# Raspi_Photometer_v2.net
KiCad netlist of a schematic drawn in EAGLE
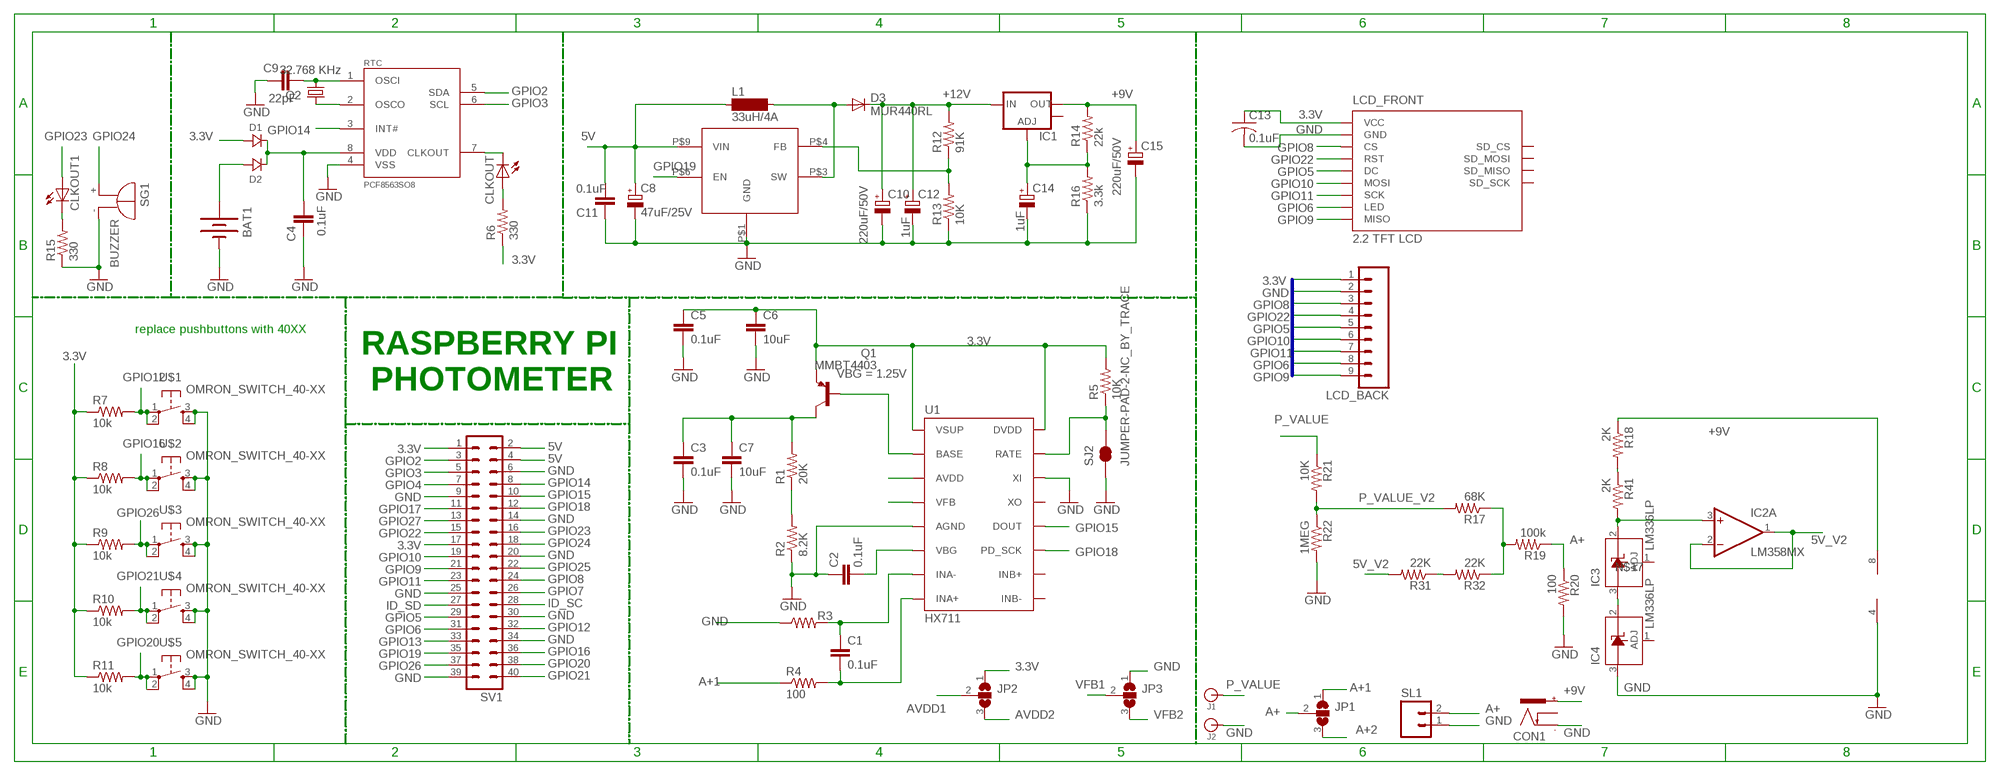
[diagram p0: schematic, sheet 1]

(export (version "E")
  (design (tool "Eeschema 10.0.6"))
  (components
    (comp (ref "BAT1")
      (value "BATTERY20PTH")
      (footprint "eagle-import:BATTCOM_20MM_PTH")
      (libsource (lib "eagle-import") (part "BATTERY20PTH"))
    )
    (comp (ref "C1")
      (value "0.1uF")
      (footprint "eagle-import:0603-CAP")
      (libsource (lib "eagle-import") (part "0.1UF-25V-5%(0603)"))
    )
    (comp (ref "C2")
      (value "0.1uF")
      (footprint "eagle-import:0603-CAP")
      (libsource (lib "eagle-import") (part "0.1UF-25V-5%(0603)"))
    )
    (comp (ref "C3")
      (value "0.1uF")
      (footprint "eagle-import:0603-CAP")
      (libsource (lib "eagle-import") (part "0.1UF-25V-5%(0603)"))
    )
    (comp (ref "C4")
      (value "0.1uF")
      (footprint "eagle-import:C0805K")
      (libsource (lib "eagle-import") (part "C-EUC0805K"))
    )
    (comp (ref "C5")
      (value "0.1uF")
      (footprint "eagle-import:0603-CAP")
      (libsource (lib "eagle-import") (part "0.1UF-25V-5%(0603)"))
    )
    (comp (ref "C6")
      (value "10uF")
      (footprint "eagle-import:1210")
      (libsource (lib "eagle-import") (part "10UF50V20%(1210)"))
    )
    (comp (ref "C7")
      (value "10uF")
      (footprint "eagle-import:1210")
      (libsource (lib "eagle-import") (part "10UF50V20%(1210)"))
    )
    (comp (ref "C8")
      (value "47uF/25V")
      (footprint "eagle-import:E3,5-10")
      (libsource (lib "eagle-import") (part "CPOL-EUE3.5-10"))
    )
    (comp (ref "C9")
      (value "22pF")
      (footprint "eagle-import:C0805K")
      (libsource (lib "eagle-import") (part "C-EUC0805K"))
    )
    (comp (ref "C10")
      (value "220uF/50V")
      (footprint "eagle-import:E5-10,5")
      (libsource (lib "eagle-import") (part "CPOL-EUE5-10.5"))
    )
    (comp (ref "C11")
      (value "0.1uF")
      (footprint "eagle-import:C0603")
      (libsource (lib "eagle-import") (part "C-EUC0603"))
    )
    (comp (ref "C12")
      (value "1uF")
      (footprint "eagle-import:E2,5-5")
      (libsource (lib "eagle-import") (part "rcl (2)_CPOL-EUE2.5-5"))
    )
    (comp (ref "C13")
      (value "0.1uF")
      (footprint "eagle-import:C0805")
      (libsource (lib "eagle-import") (part "C-USC0805"))
    )
    (comp (ref "C14")
      (value "1uF")
      (footprint "eagle-import:E2,5-5")
      (libsource (lib "eagle-import") (part "rcl (2)_CPOL-EUE2.5-5"))
    )
    (comp (ref "C15")
      (value "220uF/50V")
      (footprint "eagle-import:E5-10,5")
      (libsource (lib "eagle-import") (part "CPOL-EUE5-10.5"))
    )
    (comp (ref "CLKOUT")
      (value "LED0805")
      (footprint "eagle-import:CHIPLED_0805")
      (libsource (lib "eagle-import") (part "LED0805"))
    )
    (comp (ref "CLKOUT1")
      (value "LED1206")
      (footprint "eagle-import:CHIPLED_1206")
      (libsource (lib "eagle-import") (part "LED1206"))
    )
    (comp (ref "CON1")
      (value "POWER_CON")
      (footprint "eagle-import:NEB21R")
      (libsource (lib "eagle-import") (part "POWER_CON"))
    )
    (comp (ref "D1")
      (value "SS14")
      (footprint "eagle-import:DO214")
      (libsource (lib "eagle-import") (part "SS14"))
    )
    (comp (ref "D2")
      (value "SS14")
      (footprint "eagle-import:DO214")
      (libsource (lib "eagle-import") (part "SS14"))
    )
    (comp (ref "D3")
      (value "MUR440RL")
      (footprint "eagle-import:C2673")
      (libsource (lib "eagle-import") (part "MUR440RL"))
    )
    (comp (ref "IC1")
      (value "V_REG_LM1117SOT223")
      (footprint "eagle-import:SOT223")
      (libsource (lib "eagle-import") (part "V_REG_LM1117SOT223"))
    )
    (comp (ref "IC2")
      (value "LM358MX")
      (footprint "eagle-import:SO08")
      (libsource (lib "eagle-import") (part "LM358MX"))
    )
    (comp (ref "IC3")
      (value "LM336LP")
      (footprint "eagle-import:TO92")
      (libsource (lib "eagle-import") (part "LM336LP"))
    )
    (comp (ref "IC4")
      (value "LM336LP")
      (footprint "eagle-import:TO92")
      (libsource (lib "eagle-import") (part "LM336LP"))
    )
    (comp (ref "J1")
      (value "BANANA_CONN")
      (footprint "eagle-import:BANANA_CONN")
      (libsource (lib "eagle-import") (part "BANANA_CONN"))
    )
    (comp (ref "J2")
      (value "BANANA_CONN")
      (footprint "eagle-import:BANANA_CONN")
      (libsource (lib "eagle-import") (part "BANANA_CONN"))
    )
    (comp (ref "JP1")
      (value "SJ2W")
      (footprint "eagle-import:SJ_2")
      (libsource (lib "eagle-import") (part "SJ2W"))
    )
    (comp (ref "JP2")
      (value "SJ2W")
      (footprint "eagle-import:SJ_2")
      (libsource (lib "eagle-import") (part "SJ2W"))
    )
    (comp (ref "JP3")
      (value "SJ2W")
      (footprint "eagle-import:SJ_2")
      (libsource (lib "eagle-import") (part "SJ2W"))
    )
    (comp (ref "L1")
      (value "33uH/4A")
      (footprint "eagle-import:MS85")
      (libsource (lib "eagle-import") (part "MS85"))
    )
    (comp (ref "LCD_BACK")
      (value "M09")
      (footprint "eagle-import:09P")
      (libsource (lib "eagle-import") (part "M09"))
    )
    (comp (ref "LCD_FRONT")
      (value "TFT_LCD_2.2")
      (footprint "eagle-import:TFT_LCD_2.2")
      (libsource (lib "eagle-import") (part "TFT_LCD_2.2"))
    )
    (comp (ref "Q1")
      (value "MMBT4403")
      (footprint "eagle-import:TO92-EBC")
      (libsource (lib "eagle-import") (part "-PNP-TO92-EBC2N4403"))
    )
    (comp (ref "Q2")
      (value "32.768 KHz")
      (footprint "eagle-import:TC26H")
      (libsource (lib "eagle-import") (part "CRYSTALTC26H"))
    )
    (comp (ref "R1")
      (value "20K")
      (footprint "eagle-import:0204_7")
      (libsource (lib "eagle-import") (part "R-US_0204/7"))
    )
    (comp (ref "R2")
      (value "8.2K")
      (footprint "eagle-import:0204_7")
      (libsource (lib "eagle-import") (part "R-US_0204/7"))
    )
    (comp (ref "R3")
      (value "100")
      (footprint "eagle-import:0207_15")
      (libsource (lib "eagle-import") (part "R-US_0207/15"))
    )
    (comp (ref "R4")
      (value "100")
      (footprint "eagle-import:0207_7")
      (libsource (lib "eagle-import") (part "R-US_0207/7"))
    )
    (comp (ref "R5")
      (value "10K")
      (footprint "eagle-import:0207_7")
      (libsource (lib "eagle-import") (part "R-US_0207/7"))
    )
    (comp (ref "R6")
      (value "330")
      (footprint "eagle-import:0204_7")
      (libsource (lib "eagle-import") (part "R-US_0204/7"))
    )
    (comp (ref "R7")
      (value "10k")
      (footprint "eagle-import:0204_7")
      (libsource (lib "eagle-import") (part "R-US_0204/7"))
    )
    (comp (ref "R8")
      (value "10k")
      (footprint "eagle-import:0204_7")
      (libsource (lib "eagle-import") (part "R-US_0204/7"))
    )
    (comp (ref "R9")
      (value "10k")
      (footprint "eagle-import:0204_7")
      (libsource (lib "eagle-import") (part "R-US_0204/7"))
    )
    (comp (ref "R10")
      (value "10k")
      (footprint "eagle-import:0204_7")
      (libsource (lib "eagle-import") (part "R-US_0204/7"))
    )
    (comp (ref "R11")
      (value "10k")
      (footprint "eagle-import:0204_7")
      (libsource (lib "eagle-import") (part "R-US_0204/7"))
    )
    (comp (ref "R12")
      (value "91K")
      (footprint "eagle-import:0207_7")
      (libsource (lib "eagle-import") (part "RESISTOR0207/7"))
    )
    (comp (ref "R13")
      (value "10K")
      (footprint "eagle-import:0207_7")
      (libsource (lib "eagle-import") (part "RESISTOR0207/7"))
    )
    (comp (ref "R14")
      (value "22k")
      (footprint "eagle-import:0207_7")
      (libsource (lib "eagle-import") (part "RESISTOR0207/7"))
    )
    (comp (ref "R15")
      (value "330")
      (footprint "eagle-import:0204_7")
      (libsource (lib "eagle-import") (part "R-US_0204/7"))
    )
    (comp (ref "R16")
      (value "3.3k")
      (footprint "eagle-import:0207_7")
      (libsource (lib "eagle-import") (part "RESISTOR0207/7"))
    )
    (comp (ref "R17")
      (value "68K")
      (footprint "eagle-import:0207_7")
      (libsource (lib "eagle-import") (part "RESISTOR0207/7"))
    )
    (comp (ref "R18")
      (value "2K")
      (footprint "eagle-import:0207_7")
      (libsource (lib "eagle-import") (part "RESISTOR0207/7"))
    )
    (comp (ref "R19")
      (value "100k")
      (footprint "eagle-import:0207_7")
      (libsource (lib "eagle-import") (part "RESISTOR0207/7"))
    )
    (comp (ref "R20")
      (value "100")
      (footprint "eagle-import:0207_7")
      (libsource (lib "eagle-import") (part "RESISTOR0207/7"))
    )
    (comp (ref "R21")
      (value "10K")
      (footprint "eagle-import:0207_7")
      (libsource (lib "eagle-import") (part "RESISTOR0207/7"))
    )
    (comp (ref "R22")
      (value "1MEG")
      (footprint "eagle-import:0207_7")
      (libsource (lib "eagle-import") (part "RESISTOR0207/7"))
    )
    (comp (ref "R31")
      (value "22K")
      (footprint "eagle-import:0207_7")
      (libsource (lib "eagle-import") (part "RESISTOR0207/7"))
    )
    (comp (ref "R32")
      (value "22K")
      (footprint "eagle-import:0207_7")
      (libsource (lib "eagle-import") (part "RESISTOR0207/7"))
    )
    (comp (ref "R41")
      (value "2K")
      (footprint "eagle-import:0207_7")
      (libsource (lib "eagle-import") (part "RESISTOR0207/7"))
    )
    (comp (ref "RTC")
      (value "PCF8563SO8")
      (footprint "eagle-import:SOIC8")
      (libsource (lib "eagle-import") (part "PCF8563SO8"))
    )
    (comp (ref "SG1")
      (value "BUZZER")
      (footprint "eagle-import:F_TMB")
      (libsource (lib "eagle-import") (part "BUZZER"))
    )
    (comp (ref "SJ2")
      (value "JUMPER-PAD-2-NC_BY_TRACE")
      (footprint "eagle-import:PAD-JUMPER-2-NC_BY_TRACE_YES_SILK")
      (libsource (lib "eagle-import") (part "JUMPER-PAD-2-NC_BY_TRACE"))
    )
    (comp (ref "SL1")
      (value "M02")
      (footprint "eagle-import:02P")
      (libsource (lib "eagle-import") (part "M02"))
    )
    (comp (ref "SV1")
      (value "ML40")
      (footprint "eagle-import:ML40")
      (libsource (lib "eagle-import") (part "ML40"))
    )
    (comp (ref "U$1")
      (value "OMRON_SWITCH_40-XX")
      (footprint "eagle-import:B3F-40XX")
      (libsource (lib "eagle-import") (part "OMRON_SWITCH_40-XX"))
    )
    (comp (ref "U$2")
      (value "OMRON_SWITCH_40-XX")
      (footprint "eagle-import:B3F-40XX")
      (libsource (lib "eagle-import") (part "OMRON_SWITCH_40-XX"))
    )
    (comp (ref "U$3")
      (value "OMRON_SWITCH_40-XX")
      (footprint "eagle-import:B3F-40XX")
      (libsource (lib "eagle-import") (part "OMRON_SWITCH_40-XX"))
    )
    (comp (ref "U$4")
      (value "OMRON_SWITCH_40-XX")
      (footprint "eagle-import:B3F-40XX")
      (libsource (lib "eagle-import") (part "OMRON_SWITCH_40-XX"))
    )
    (comp (ref "U$5")
      (value "OMRON_SWITCH_40-XX")
      (footprint "eagle-import:B3F-40XX")
      (libsource (lib "eagle-import") (part "OMRON_SWITCH_40-XX"))
    )
    (comp (ref "U$6")
      (value "XL6009")
      (footprint "eagle-import:TO-263-5L")
      (libsource (lib "eagle-import") (part "XL6009"))
    )
    (comp (ref "U1")
      (value "HX711")
      (footprint "eagle-import:SO16")
      (libsource (lib "eagle-import") (part "HX711HX711"))
    )
  )
  (nets
    (net (code "1") (name "/+9V") (class "Default")
      (node (ref "C15") (pin "+") (pinfunction "+_+") (pintype "passive"))
      (node (ref "CON1") (pin "+") (pinfunction "+_+") (pintype "passive"))
      (node (ref "IC1") (pin "2") (pinfunction "OUT_2") (pintype "output"))
      (node (ref "IC2") (pin "8") (pinfunction "V+_8") (pintype "power_in"))
      (node (ref "R14") (pin "2") (pinfunction "2_2") (pintype "passive"))
      (node (ref "R18") (pin "1") (pinfunction "1_1") (pintype "passive"))
    )
    (net (code "2") (name "/+12V") (class "Default")
      (node (ref "C10") (pin "+") (pinfunction "+_+") (pintype "passive"))
      (node (ref "C12") (pin "+") (pinfunction "+_+") (pintype "passive"))
      (node (ref "D3") (pin "C") (pinfunction "C_C") (pintype "passive"))
      (node (ref "IC1") (pin "3") (pinfunction "IN_3") (pintype "input"))
      (node (ref "R12") (pin "2") (pinfunction "2_2") (pintype "passive"))
    )
    (net (code "3") (name "/3.3V") (class "Default")
      (node (ref "C13") (pin "1") (pinfunction "1_1") (pintype "passive"))
      (node (ref "C5") (pin "1") (pinfunction "1_1") (pintype "passive"))
      (node (ref "C6") (pin "1") (pinfunction "1_1") (pintype "passive"))
      (node (ref "D1") (pin "ANODE") (pinfunction "ANODE_ANODE") (pintype "bidirectional"))
      (node (ref "JP2") (pin "1") (pinfunction "1_1") (pintype "passive"))
      (node (ref "LCD_BACK") (pin "1") (pinfunction "1_1") (pintype "passive"))
      (node (ref "LCD_FRONT") (pin "VCC") (pinfunction "VCC_VCC") (pintype "power_in"))
      (node (ref "Q1") (pin "E") (pinfunction "E_E") (pintype "passive"))
      (node (ref "R10") (pin "1") (pinfunction "1_1") (pintype "passive"))
      (node (ref "R11") (pin "1") (pinfunction "1_1") (pintype "passive"))
      (node (ref "R5") (pin "2") (pinfunction "2_2") (pintype "passive"))
      (node (ref "R6") (pin "1") (pinfunction "1_1") (pintype "passive"))
      (node (ref "R7") (pin "1") (pinfunction "1_1") (pintype "passive"))
      (node (ref "R8") (pin "1") (pinfunction "1_1") (pintype "passive"))
      (node (ref "R9") (pin "1") (pinfunction "1_1") (pintype "passive"))
      (node (ref "SV1") (pin "1") (pinfunction "1_1") (pintype "passive"))
      (node (ref "SV1") (pin "17") (pinfunction "17_17") (pintype "passive"))
      (node (ref "U1") (pin "1") (pinfunction "VSUP_1") (pintype "bidirectional"))
      (node (ref "U1") (pin "16") (pinfunction "DVDD_16") (pintype "bidirectional"))
    )
    (net (code "4") (name "/5V") (class "Default")
      (node (ref "C11") (pin "2") (pinfunction "2_2") (pintype "passive"))
      (node (ref "C8") (pin "+") (pinfunction "+_+") (pintype "passive"))
      (node (ref "L1") (pin "1") (pinfunction "1_1") (pintype "passive"))
      (node (ref "SV1") (pin "2") (pinfunction "2_2") (pintype "passive"))
      (node (ref "SV1") (pin "4") (pinfunction "4_4") (pintype "passive"))
      (node (ref "U$6") (pin "P$9") (pinfunction "VIN_P$9") (pintype "bidirectional"))
    )
    (net (code "5") (name "/5V_V2") (class "Default")
      (node (ref "IC2") (pin "1") (pinfunction "OUT_1") (pintype "output"))
      (node (ref "IC2") (pin "2") (pinfunction "-IN_2") (pintype "input"))
      (node (ref "R31") (pin "2") (pinfunction "2_2") (pintype "passive"))
    )
    (net (code "6") (name "/A+") (class "Default")
      (node (ref "JP1") (pin "2") (pinfunction "2_2") (pintype "passive"))
      (node (ref "R19") (pin "1") (pinfunction "1_1") (pintype "passive"))
      (node (ref "R20") (pin "1") (pinfunction "1_1") (pintype "passive"))
      (node (ref "SL1") (pin "2") (pinfunction "2_2") (pintype "passive"))
    )
    (net (code "7") (name "/A+1") (class "Default")
      (node (ref "JP1") (pin "1") (pinfunction "1_1") (pintype "passive"))
      (node (ref "R4") (pin "1") (pinfunction "1_1") (pintype "passive"))
    )
    (net (code "8") (name "/A+2") (class "Default")
      (node (ref "JP1") (pin "3") (pinfunction "3_3") (pintype "passive"))
    )
    (net (code "9") (name "/AVDD1") (class "Default")
      (node (ref "JP2") (pin "2") (pinfunction "2_2") (pintype "passive"))
      (node (ref "U1") (pin "3") (pinfunction "AVDD_3") (pintype "bidirectional"))
    )
    (net (code "10") (name "/AVDD2") (class "Default")
      (node (ref "C3") (pin "1") (pinfunction "1_1") (pintype "passive"))
      (node (ref "C7") (pin "1") (pinfunction "1_1") (pintype "passive"))
      (node (ref "JP2") (pin "3") (pinfunction "3_3") (pintype "passive"))
      (node (ref "Q1") (pin "C") (pinfunction "C_C") (pintype "passive"))
      (node (ref "R1") (pin "2") (pinfunction "2_2") (pintype "passive"))
    )
    (net (code "11") (name "/GPIO2") (class "Default")
      (node (ref "RTC") (pin "5") (pinfunction "SDA_5") (pintype "bidirectional"))
      (node (ref "SV1") (pin "3") (pinfunction "3_3") (pintype "passive"))
    )
    (net (code "12") (name "/GPIO3") (class "Default")
      (node (ref "RTC") (pin "6") (pinfunction "SCL_6") (pintype "bidirectional"))
      (node (ref "SV1") (pin "5") (pinfunction "5_5") (pintype "passive"))
    )
    (net (code "13") (name "/GPIO4") (class "Default")
      (node (ref "SV1") (pin "7") (pinfunction "7_7") (pintype "passive"))
    )
    (net (code "14") (name "/GPIO5") (class "Default")
      (node (ref "LCD_BACK") (pin "5") (pinfunction "5_5") (pintype "passive"))
      (node (ref "LCD_FRONT") (pin "DC") (pinfunction "DC_DC") (pintype "bidirectional"))
      (node (ref "SV1") (pin "29") (pinfunction "29_29") (pintype "passive"))
    )
    (net (code "15") (name "/GPIO6") (class "Default")
      (node (ref "LCD_BACK") (pin "8") (pinfunction "8_8") (pintype "passive"))
      (node (ref "LCD_FRONT") (pin "LED") (pinfunction "LED_LED") (pintype "bidirectional"))
      (node (ref "SV1") (pin "31") (pinfunction "31_31") (pintype "passive"))
    )
    (net (code "16") (name "/GPIO7") (class "Default")
      (node (ref "SV1") (pin "26") (pinfunction "26_26") (pintype "passive"))
    )
    (net (code "17") (name "/GPIO8") (class "Default")
      (node (ref "LCD_BACK") (pin "3") (pinfunction "3_3") (pintype "passive"))
      (node (ref "LCD_FRONT") (pin "CS") (pinfunction "CS_CS") (pintype "bidirectional"))
      (node (ref "SV1") (pin "24") (pinfunction "24_24") (pintype "passive"))
    )
    (net (code "18") (name "/GPIO9") (class "Default")
      (node (ref "LCD_BACK") (pin "9") (pinfunction "9_9") (pintype "passive"))
      (node (ref "LCD_FRONT") (pin "MISO") (pinfunction "MISO_MISO") (pintype "bidirectional"))
      (node (ref "SV1") (pin "21") (pinfunction "21_21") (pintype "passive"))
    )
    (net (code "19") (name "/GPIO10") (class "Default")
      (node (ref "LCD_BACK") (pin "6") (pinfunction "6_6") (pintype "passive"))
      (node (ref "LCD_FRONT") (pin "MOSI") (pinfunction "MOSI_MOSI") (pintype "bidirectional"))
      (node (ref "SV1") (pin "19") (pinfunction "19_19") (pintype "passive"))
    )
    (net (code "20") (name "/GPIO11") (class "Default")
      (node (ref "LCD_BACK") (pin "7") (pinfunction "7_7") (pintype "passive"))
      (node (ref "LCD_FRONT") (pin "SCK") (pinfunction "SCK_SCK") (pintype "bidirectional"))
      (node (ref "SV1") (pin "23") (pinfunction "23_23") (pintype "passive"))
    )
    (net (code "21") (name "/GPIO12") (class "Default")
      (node (ref "R7") (pin "2") (pinfunction "2_2") (pintype "passive"))
      (node (ref "SV1") (pin "32") (pinfunction "32_32") (pintype "passive"))
      (node (ref "U$1") (pin "1") (pinfunction "P_1") (pintype "passive"))
      (node (ref "U$1") (pin "2") (pinfunction "P1_2") (pintype "passive"))
    )
    (net (code "22") (name "/GPIO13") (class "Default")
      (node (ref "SV1") (pin "33") (pinfunction "33_33") (pintype "passive"))
    )
    (net (code "23") (name "/GPIO14") (class "Default")
      (node (ref "RTC") (pin "3") (pinfunction "INT#_3") (pintype "bidirectional"))
      (node (ref "SV1") (pin "8") (pinfunction "8_8") (pintype "passive"))
    )
    (net (code "24") (name "/GPIO15") (class "Default")
      (node (ref "SV1") (pin "10") (pinfunction "10_10") (pintype "passive"))
      (node (ref "U1") (pin "12") (pinfunction "DOUT_12") (pintype "bidirectional"))
    )
    (net (code "25") (name "/GPIO16") (class "Default")
      (node (ref "R8") (pin "2") (pinfunction "2_2") (pintype "passive"))
      (node (ref "SV1") (pin "36") (pinfunction "36_36") (pintype "passive"))
      (node (ref "U$2") (pin "1") (pinfunction "P_1") (pintype "passive"))
      (node (ref "U$2") (pin "2") (pinfunction "P1_2") (pintype "passive"))
    )
    (net (code "26") (name "/GPIO17") (class "Default")
      (node (ref "SV1") (pin "11") (pinfunction "11_11") (pintype "passive"))
    )
    (net (code "27") (name "/GPIO18") (class "Default")
      (node (ref "SV1") (pin "12") (pinfunction "12_12") (pintype "passive"))
      (node (ref "U1") (pin "11") (pinfunction "PD_SCK_11") (pintype "bidirectional"))
    )
    (net (code "28") (name "/GPIO19") (class "Default")
      (node (ref "SV1") (pin "35") (pinfunction "35_35") (pintype "passive"))
      (node (ref "U$6") (pin "P$6") (pinfunction "EN_P$6") (pintype "bidirectional"))
    )
    (net (code "29") (name "/GPIO20") (class "Default")
      (node (ref "R11") (pin "2") (pinfunction "2_2") (pintype "passive"))
      (node (ref "SV1") (pin "38") (pinfunction "38_38") (pintype "passive"))
      (node (ref "U$5") (pin "1") (pinfunction "P_1") (pintype "passive"))
      (node (ref "U$5") (pin "2") (pinfunction "P1_2") (pintype "passive"))
    )
    (net (code "30") (name "/GPIO21") (class "Default")
      (node (ref "R10") (pin "2") (pinfunction "2_2") (pintype "passive"))
      (node (ref "SV1") (pin "40") (pinfunction "40_40") (pintype "passive"))
      (node (ref "U$4") (pin "1") (pinfunction "P_1") (pintype "passive"))
      (node (ref "U$4") (pin "2") (pinfunction "P1_2") (pintype "passive"))
    )
    (net (code "31") (name "/GPIO22") (class "Default")
      (node (ref "LCD_BACK") (pin "4") (pinfunction "4_4") (pintype "passive"))
      (node (ref "LCD_FRONT") (pin "RST") (pinfunction "RST_RST") (pintype "bidirectional"))
      (node (ref "SV1") (pin "15") (pinfunction "15_15") (pintype "passive"))
    )
    (net (code "32") (name "/GPIO23") (class "Default")
      (node (ref "CLKOUT1") (pin "A") (pinfunction "A_A") (pintype "passive"))
      (node (ref "SV1") (pin "16") (pinfunction "16_16") (pintype "passive"))
    )
    (net (code "33") (name "/GPIO24") (class "Default")
      (node (ref "SG1") (pin "+") (pinfunction "+_+") (pintype "passive"))
      (node (ref "SV1") (pin "18") (pinfunction "18_18") (pintype "passive"))
    )
    (net (code "34") (name "/GPIO25") (class "Default")
      (node (ref "SV1") (pin "22") (pinfunction "22_22") (pintype "passive"))
    )
    (net (code "35") (name "/GPIO26") (class "Default")
      (node (ref "R9") (pin "2") (pinfunction "2_2") (pintype "passive"))
      (node (ref "SV1") (pin "37") (pinfunction "37_37") (pintype "passive"))
      (node (ref "U$3") (pin "1") (pinfunction "P_1") (pintype "passive"))
      (node (ref "U$3") (pin "2") (pinfunction "P1_2") (pintype "passive"))
    )
    (net (code "36") (name "/GPIO27") (class "Default")
      (node (ref "SV1") (pin "13") (pinfunction "13_13") (pintype "passive"))
    )
    (net (code "37") (name "/ID_SC") (class "Default")
      (node (ref "SV1") (pin "28") (pinfunction "28_28") (pintype "passive"))
    )
    (net (code "38") (name "/ID_SD") (class "Default")
      (node (ref "SV1") (pin "27") (pinfunction "27_27") (pintype "passive"))
    )
    (net (code "39") (name "/N$17") (class "Default")
      (node (ref "IC2") (pin "3") (pinfunction "+IN_3") (pintype "input"))
      (node (ref "IC3") (pin "2") (pinfunction "C_2") (pintype "passive"))
      (node (ref "R41") (pin "2") (pinfunction "2_2") (pintype "passive"))
    )
    (net (code "40") (name "/P_VALUE") (class "Default")
      (node (ref "J1") (pin "P$2") (pinfunction "1_P$2") (pintype "passive"))
      (node (ref "R21") (pin "1") (pinfunction "1_1") (pintype "passive"))
    )
    (net (code "41") (name "/P_VALUE_V2") (class "Default")
      (node (ref "R17") (pin "2") (pinfunction "2_2") (pintype "passive"))
      (node (ref "R21") (pin "2") (pinfunction "2_2") (pintype "passive"))
      (node (ref "R22") (pin "1") (pinfunction "1_1") (pintype "passive"))
    )
    (net (code "42") (name "/VFB1") (class "Default")
      (node (ref "JP3") (pin "2") (pinfunction "2_2") (pintype "passive"))
      (node (ref "U1") (pin "4") (pinfunction "VFB_4") (pintype "bidirectional"))
    )
    (net (code "43") (name "/VFB2") (class "Default")
      (node (ref "JP3") (pin "3") (pinfunction "3_3") (pintype "passive"))
      (node (ref "R1") (pin "1") (pinfunction "1_1") (pintype "passive"))
      (node (ref "R2") (pin "2") (pinfunction "2_2") (pintype "passive"))
    )
    (net (code "44") (name "GND") (class "Default")
      (node (ref "BAT1") (pin "2") (pinfunction "-_2") (pintype "power_in"))
      (node (ref "C10") (pin "-") (pinfunction "-_-") (pintype "passive"))
      (node (ref "C11") (pin "1") (pinfunction "1_1") (pintype "passive"))
      (node (ref "C12") (pin "-") (pinfunction "-_-") (pintype "passive"))
      (node (ref "C13") (pin "2") (pinfunction "2_2") (pintype "passive"))
      (node (ref "C14") (pin "-") (pinfunction "-_-") (pintype "passive"))
      (node (ref "C15") (pin "-") (pinfunction "-_-") (pintype "passive"))
      (node (ref "C2") (pin "1") (pinfunction "1_1") (pintype "passive"))
      (node (ref "C3") (pin "2") (pinfunction "2_2") (pintype "passive"))
      (node (ref "C4") (pin "1") (pinfunction "1_1") (pintype "passive"))
      (node (ref "C5") (pin "2") (pinfunction "2_2") (pintype "passive"))
      (node (ref "C6") (pin "2") (pinfunction "2_2") (pintype "passive"))
      (node (ref "C7") (pin "2") (pinfunction "2_2") (pintype "passive"))
      (node (ref "C8") (pin "-") (pinfunction "-_-") (pintype "passive"))
      (node (ref "C9") (pin "1") (pinfunction "1_1") (pintype "passive"))
      (node (ref "CON1") (pin "-") (pinfunction "-_-") (pintype "passive"))
      (node (ref "IC2") (pin "4") (pinfunction "V-_4") (pintype "power_in"))
      (node (ref "IC4") (pin "3") (pinfunction "A_3") (pintype "input"))
      (node (ref "J2") (pin "P$2") (pinfunction "1_P$2") (pintype "passive"))
      (node (ref "JP3") (pin "1") (pinfunction "1_1") (pintype "passive"))
      (node (ref "LCD_BACK") (pin "2") (pinfunction "2_2") (pintype "passive"))
      (node (ref "LCD_FRONT") (pin "GND") (pinfunction "GND_GND") (pintype "power_in"))
      (node (ref "R13") (pin "1") (pinfunction "1_1") (pintype "passive"))
      (node (ref "R15") (pin "1") (pinfunction "1_1") (pintype "passive"))
      (node (ref "R16") (pin "1") (pinfunction "1_1") (pintype "passive"))
      (node (ref "R2") (pin "1") (pinfunction "1_1") (pintype "passive"))
      (node (ref "R20") (pin "2") (pinfunction "2_2") (pintype "passive"))
      (node (ref "R22") (pin "2") (pinfunction "2_2") (pintype "passive"))
      (node (ref "R3") (pin "1") (pinfunction "1_1") (pintype "passive"))
      (node (ref "RTC") (pin "4") (pinfunction "VSS_4") (pintype "bidirectional"))
      (node (ref "SG1") (pin "-") (pinfunction "-_-") (pintype "passive"))
      (node (ref "SJ2") (pin "1") (pinfunction "1_1") (pintype "passive"))
      (node (ref "SL1") (pin "1") (pinfunction "1_1") (pintype "passive"))
      (node (ref "SV1") (pin "14") (pinfunction "14_14") (pintype "passive"))
      (node (ref "SV1") (pin "20") (pinfunction "20_20") (pintype "passive"))
      (node (ref "SV1") (pin "25") (pinfunction "25_25") (pintype "passive"))
      (node (ref "SV1") (pin "30") (pinfunction "30_30") (pintype "passive"))
      (node (ref "SV1") (pin "34") (pinfunction "34_34") (pintype "passive"))
      (node (ref "SV1") (pin "39") (pinfunction "39_39") (pintype "passive"))
      (node (ref "SV1") (pin "6") (pinfunction "6_6") (pintype "passive"))
      (node (ref "SV1") (pin "9") (pinfunction "9_9") (pintype "passive"))
      (node (ref "U$1") (pin "3") (pinfunction "S_3") (pintype "passive"))
      (node (ref "U$1") (pin "4") (pinfunction "S1_4") (pintype "passive"))
      (node (ref "U$2") (pin "3") (pinfunction "S_3") (pintype "passive"))
      (node (ref "U$2") (pin "4") (pinfunction "S1_4") (pintype "passive"))
      (node (ref "U$3") (pin "3") (pinfunction "S_3") (pintype "passive"))
      (node (ref "U$3") (pin "4") (pinfunction "S1_4") (pintype "passive"))
      (node (ref "U$4") (pin "3") (pinfunction "S_3") (pintype "passive"))
      (node (ref "U$4") (pin "4") (pinfunction "S1_4") (pintype "passive"))
      (node (ref "U$5") (pin "3") (pinfunction "S_3") (pintype "passive"))
      (node (ref "U$5") (pin "4") (pinfunction "S1_4") (pintype "passive"))
      (node (ref "U$6") (pin "P$1") (pinfunction "GND_P$1") (pintype "bidirectional"))
      (node (ref "U1") (pin "14") (pinfunction "XI_14") (pintype "bidirectional"))
      (node (ref "U1") (pin "5") (pinfunction "AGND_5") (pintype "bidirectional"))
    )
    (net (code "45") (name "Net-(BAT1-+)") (class "Default")
      (node (ref "BAT1") (pin "1") (pinfunction "+_1") (pintype "power_in"))
      (node (ref "D2") (pin "ANODE") (pinfunction "ANODE_ANODE") (pintype "bidirectional"))
    )
    (net (code "46") (name "Net-(CLKOUT-PadA)") (class "Default")
      (node (ref "CLKOUT") (pin "A") (pinfunction "A_A") (pintype "passive"))
      (node (ref "R6") (pin "2") (pinfunction "2_2") (pintype "passive"))
    )
    (net (code "47") (name "Net-(CLKOUT1-PadC)") (class "Default")
      (node (ref "CLKOUT1") (pin "C") (pinfunction "C_C") (pintype "passive"))
      (node (ref "R15") (pin "2") (pinfunction "2_2") (pintype "passive"))
    )
    (net (code "48") (name "Net-(IC1-ADJ)") (class "Default")
      (node (ref "C14") (pin "+") (pinfunction "+_+") (pintype "passive"))
      (node (ref "IC1") (pin "1") (pinfunction "ADJ_1") (pintype "input"))
      (node (ref "R14") (pin "1") (pinfunction "1_1") (pintype "passive"))
      (node (ref "R16") (pin "2") (pinfunction "2_2") (pintype "passive"))
    )
    (net (code "49") (name "Net-(IC3-A)") (class "Default")
      (node (ref "IC3") (pin "3") (pinfunction "A_3") (pintype "input"))
      (node (ref "IC4") (pin "2") (pinfunction "C_2") (pintype "passive"))
    )
    (net (code "50") (name "Net-(R17-Pad1)") (class "Default")
      (node (ref "R17") (pin "1") (pinfunction "1_1") (pintype "passive"))
      (node (ref "R19") (pin "2") (pinfunction "2_2") (pintype "passive"))
      (node (ref "R32") (pin "1") (pinfunction "1_1") (pintype "passive"))
    )
    (net (code "51") (name "Net-(R18-Pad2)") (class "Default")
      (node (ref "R18") (pin "2") (pinfunction "2_2") (pintype "passive"))
      (node (ref "R41") (pin "1") (pinfunction "1_1") (pintype "passive"))
    )
    (net (code "52") (name "Net-(R31-Pad1)") (class "Default")
      (node (ref "R31") (pin "1") (pinfunction "1_1") (pintype "passive"))
      (node (ref "R32") (pin "2") (pinfunction "2_2") (pintype "passive"))
    )
    (net (code "53") (name "Net-(RTC-CLKOUT)") (class "Default")
      (node (ref "CLKOUT") (pin "C") (pinfunction "C_C") (pintype "passive"))
      (node (ref "RTC") (pin "7") (pinfunction "CLKOUT_7") (pintype "bidirectional"))
    )
    (net (code "54") (name "Net-(RTC-OSCI)") (class "Default")
      (node (ref "C9") (pin "2") (pinfunction "2_2") (pintype "passive"))
      (node (ref "Q2") (pin "1") (pinfunction "1_1") (pintype "passive"))
      (node (ref "RTC") (pin "1") (pinfunction "OSCI_1") (pintype "bidirectional"))
    )
    (net (code "55") (name "Net-(RTC-OSCO)") (class "Default")
      (node (ref "Q2") (pin "2") (pinfunction "2_2") (pintype "passive"))
      (node (ref "RTC") (pin "2") (pinfunction "OSCO_2") (pintype "bidirectional"))
    )
    (net (code "56") (name "Net-(RTC-VDD)") (class "Default")
      (node (ref "C4") (pin "2") (pinfunction "2_2") (pintype "passive"))
      (node (ref "D1") (pin "CATHODE") (pinfunction "CATHODE_CATHODE") (pintype "bidirectional"))
      (node (ref "D2") (pin "CATHODE") (pinfunction "CATHODE_CATHODE") (pintype "bidirectional"))
      (node (ref "RTC") (pin "8") (pinfunction "VDD_8") (pintype "bidirectional"))
    )
    (net (code "57") (name "Net-(U$6-FB)") (class "Default")
      (node (ref "R12") (pin "1") (pinfunction "1_1") (pintype "passive"))
      (node (ref "R13") (pin "2") (pinfunction "2_2") (pintype "passive"))
      (node (ref "U$6") (pin "P$4") (pinfunction "FB_P$4") (pintype "bidirectional"))
    )
    (net (code "58") (name "Net-(U$6-SW)") (class "Default")
      (node (ref "D3") (pin "A") (pinfunction "A_A") (pintype "passive"))
      (node (ref "L1") (pin "2") (pinfunction "2_2") (pintype "passive"))
      (node (ref "U$6") (pin "P$3") (pinfunction "SW_P$3") (pintype "bidirectional"))
    )
    (net (code "59") (name "Net-(U1-BASE)") (class "Default")
      (node (ref "Q1") (pin "B") (pinfunction "B_B") (pintype "passive"))
      (node (ref "U1") (pin "2") (pinfunction "BASE_2") (pintype "bidirectional"))
    )
    (net (code "60") (name "Net-(U1-INA+)") (class "Default")
      (node (ref "C1") (pin "2") (pinfunction "2_2") (pintype "passive"))
      (node (ref "R4") (pin "2") (pinfunction "2_2") (pintype "passive"))
      (node (ref "U1") (pin "8") (pinfunction "INA+_8") (pintype "bidirectional"))
    )
    (net (code "61") (name "Net-(U1-INA-)") (class "Default")
      (node (ref "C1") (pin "1") (pinfunction "1_1") (pintype "passive"))
      (node (ref "R3") (pin "2") (pinfunction "2_2") (pintype "passive"))
      (node (ref "U1") (pin "7") (pinfunction "INA-_7") (pintype "bidirectional"))
    )
    (net (code "62") (name "Net-(U1-RATE)") (class "Default")
      (node (ref "R5") (pin "1") (pinfunction "1_1") (pintype "passive"))
      (node (ref "SJ2") (pin "2") (pinfunction "2_2") (pintype "passive"))
      (node (ref "U1") (pin "15") (pinfunction "RATE_15") (pintype "bidirectional"))
    )
    (net (code "63") (name "Net-(U1-VBG)") (class "Default")
      (node (ref "C2") (pin "2") (pinfunction "2_2") (pintype "passive"))
      (node (ref "U1") (pin "6") (pinfunction "VBG_6") (pintype "bidirectional"))
    )
    (net (code "64") (name "unconnected-(CON1-PadC)") (class "Default")
      (node (ref "CON1") (pin "C") (pinfunction "C_C") (pintype "passive"))
    )
    (net (code "65") (name "unconnected-(IC1-OUT-Pad4)") (class "Default")
      (node (ref "IC1") (pin "4") (pinfunction "OUT_4") (pintype "output"))
    )
    (net (code "66") (name "unconnected-(IC3-ADJ-Pad1)") (class "Default")
      (node (ref "IC3") (pin "1") (pinfunction "ADJ_1") (pintype "input"))
    )
    (net (code "67") (name "unconnected-(IC4-ADJ-Pad1)") (class "Default")
      (node (ref "IC4") (pin "1") (pinfunction "ADJ_1") (pintype "input"))
    )
    (net (code "68") (name "unconnected-(LCD_FRONT-PadSD_CS)") (class "Default")
      (node (ref "LCD_FRONT") (pin "SD_CS") (pinfunction "SD_CS_SD_CS") (pintype "bidirectional"))
    )
    (net (code "69") (name "unconnected-(LCD_FRONT-PadSD_MISO)") (class "Default")
      (node (ref "LCD_FRONT") (pin "SD_MISO") (pinfunction "SD_MISO_SD_MISO") (pintype "bidirectional"))
    )
    (net (code "70") (name "unconnected-(LCD_FRONT-PadSD_MOSI)") (class "Default")
      (node (ref "LCD_FRONT") (pin "SD_MOSI") (pinfunction "SD_MOSI_SD_MOSI") (pintype "bidirectional"))
    )
    (net (code "71") (name "unconnected-(LCD_FRONT-PadSD_SCK)") (class "Default")
      (node (ref "LCD_FRONT") (pin "SD_SCK") (pinfunction "SD_SCK_SD_SCK") (pintype "bidirectional"))
    )
    (net (code "72") (name "unconnected-(U1-INB+-Pad10)") (class "Default")
      (node (ref "U1") (pin "10") (pinfunction "INB+_10") (pintype "bidirectional"))
    )
    (net (code "73") (name "unconnected-(U1-INB--Pad9)") (class "Default")
      (node (ref "U1") (pin "9") (pinfunction "INB-_9") (pintype "bidirectional"))
    )
    (net (code "74") (name "unconnected-(U1-XO-Pad13)") (class "Default")
      (node (ref "U1") (pin "13") (pinfunction "XO_13") (pintype "bidirectional"))
    )
  )
)
